# voltage_sensing.net
KiCad netlist of a schematic drawn in Altium Designer
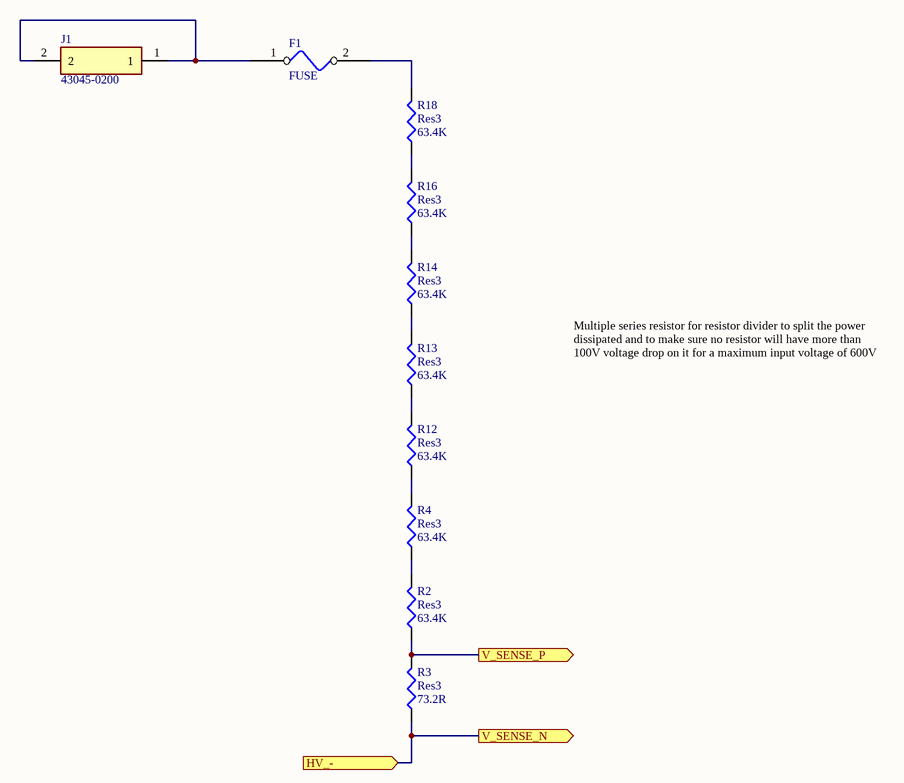
[diagram p0: voltage_sensing.SchDoc]

(export (version "E")
  (design (tool "Eeschema 10.0.6"))
  (components
    (comp (ref "F1") (value "FUSE") (footprint "12Z-2010") (libsource (lib "esd_library") (part "FUSE")))
    (comp (ref "J1")
      (value "43045-0200")
      (footprint "MOLEX_43045-0200")
      (description "Connector Header Through Hole, Right Angle 2 position -")
      (fields (field (name "MF") "Molex") (field (name "DIGI-KEY_PART_NUMBER") "WM1813-ND"))
      (libsource (lib "43045-0200") (part "43045-0200"))
    )
    (comp (ref "R2")
      (value "Res3")
      (footprint "RESC2112X05M")
      (description "RES SMD 63.4K OHM 1% 1/8W 0805")
      (fields (field (name "ALTIUM_VALUE") "63.4K") (field (name "MPN") "CRCW080563K4FKEA"))
      (libsource (lib "esd_library") (part "Resistor_63.4K"))
    )
    (comp (ref "R3")
      (value "Res3")
      (footprint "RESC2112X05M")
      (description "RES SMD 73.2R OHM 1% 1/8W 0805")
      (fields (field (name "ALTIUM_VALUE") "73.2R") (field (name "MPN") "CRCW080573R2FKEA"))
      (libsource (lib "esd_library") (part "Resistor_73.2R"))
    )
    (comp (ref "R4")
      (value "Res3")
      (footprint "RESC2112X05M")
      (description "RES SMD 63.4K OHM 1% 1/8W 0805")
      (fields (field (name "ALTIUM_VALUE") "63.4K") (field (name "MPN") "CRCW080563K4FKEA"))
      (libsource (lib "esd_library") (part "Resistor_63.4K"))
    )
    (comp (ref "R12")
      (value "Res3")
      (footprint "RESC2112X05M")
      (description "RES SMD 63.4K OHM 1% 1/8W 0805")
      (fields (field (name "ALTIUM_VALUE") "63.4K") (field (name "MPN") "CRCW080563K4FKEA"))
      (libsource (lib "esd_library") (part "Resistor_63.4K"))
    )
    (comp (ref "R13")
      (value "Res3")
      (footprint "RESC2112X05M")
      (description "RES SMD 63.4K OHM 1% 1/8W 0805")
      (fields (field (name "ALTIUM_VALUE") "63.4K") (field (name "MPN") "CRCW080563K4FKEA"))
      (libsource (lib "esd_library") (part "Resistor_63.4K"))
    )
    (comp (ref "R14")
      (value "Res3")
      (footprint "RESC2112X05M")
      (description "RES SMD 63.4K OHM 1% 1/8W 0805")
      (fields (field (name "ALTIUM_VALUE") "63.4K") (field (name "MPN") "CRCW080563K4FKEA"))
      (libsource (lib "esd_library") (part "Resistor_63.4K"))
    )
    (comp (ref "R16")
      (value "Res3")
      (footprint "RESC2112X05M")
      (description "RES SMD 63.4K OHM 1% 1/8W 0805")
      (fields (field (name "ALTIUM_VALUE") "63.4K") (field (name "MPN") "CRCW080563K4FKEA"))
      (libsource (lib "esd_library") (part "Resistor_63.4K"))
    )
    (comp (ref "R18")
      (value "Res3")
      (footprint "RESC2112X05M")
      (description "RES SMD 63.4K OHM 1% 1/8W 0805")
      (fields (field (name "ALTIUM_VALUE") "63.4K") (field (name "MPN") "CRCW080563K4FKEA"))
      (libsource (lib "esd_library") (part "Resistor_63.4K"))
    )
  )
  (nets
    (net (code "1") (name "/HV_-") (class "Default")
      (node (ref "R3") (pin "1") (pinfunction "1_1") (pintype "passive"))
    )
    (net (code "2") (name "/V_SENSE_P") (class "Default")
      (node (ref "R2") (pin "1") (pinfunction "1_1") (pintype "passive"))
      (node (ref "R3") (pin "2") (pinfunction "2_2") (pintype "passive"))
    )
    (net (code "3") (name "Net-(F1-Pad1)") (class "Default")
      (node (ref "F1") (pin "1") (pinfunction "1_1") (pintype "passive"))
      (node (ref "J1") (pin "1") (pinfunction "1_1") (pintype "passive"))
      (node (ref "J1") (pin "2") (pinfunction "2_2") (pintype "passive"))
    )
    (net (code "4") (name "Net-(F1-Pad2)") (class "Default")
      (node (ref "F1") (pin "2") (pinfunction "2_2") (pintype "passive"))
      (node (ref "R18") (pin "2") (pinfunction "2_2") (pintype "passive"))
    )
    (net (code "5") (name "Net-(R2-Pad2)") (class "Default")
      (node (ref "R2") (pin "2") (pinfunction "2_2") (pintype "passive"))
      (node (ref "R4") (pin "1") (pinfunction "1_1") (pintype "passive"))
    )
    (net (code "6") (name "Net-(R12-Pad1)") (class "Default")
      (node (ref "R12") (pin "1") (pinfunction "1_1") (pintype "passive"))
      (node (ref "R4") (pin "2") (pinfunction "2_2") (pintype "passive"))
    )
    (net (code "7") (name "Net-(R12-Pad2)") (class "Default")
      (node (ref "R12") (pin "2") (pinfunction "2_2") (pintype "passive"))
      (node (ref "R13") (pin "1") (pinfunction "1_1") (pintype "passive"))
    )
    (net (code "8") (name "Net-(R13-Pad2)") (class "Default")
      (node (ref "R13") (pin "2") (pinfunction "2_2") (pintype "passive"))
      (node (ref "R14") (pin "1") (pinfunction "1_1") (pintype "passive"))
    )
    (net (code "9") (name "Net-(R14-Pad2)") (class "Default")
      (node (ref "R14") (pin "2") (pinfunction "2_2") (pintype "passive"))
      (node (ref "R16") (pin "1") (pinfunction "1_1") (pintype "passive"))
    )
    (net (code "10") (name "Net-(R16-Pad2)") (class "Default")
      (node (ref "R16") (pin "2") (pinfunction "2_2") (pintype "passive"))
      (node (ref "R18") (pin "1") (pinfunction "1_1") (pintype "passive"))
    )
  )
)
